# NE556-CD4069-Synth-Toy.net
KiCad netlist of a schematic drawn in EAGLE
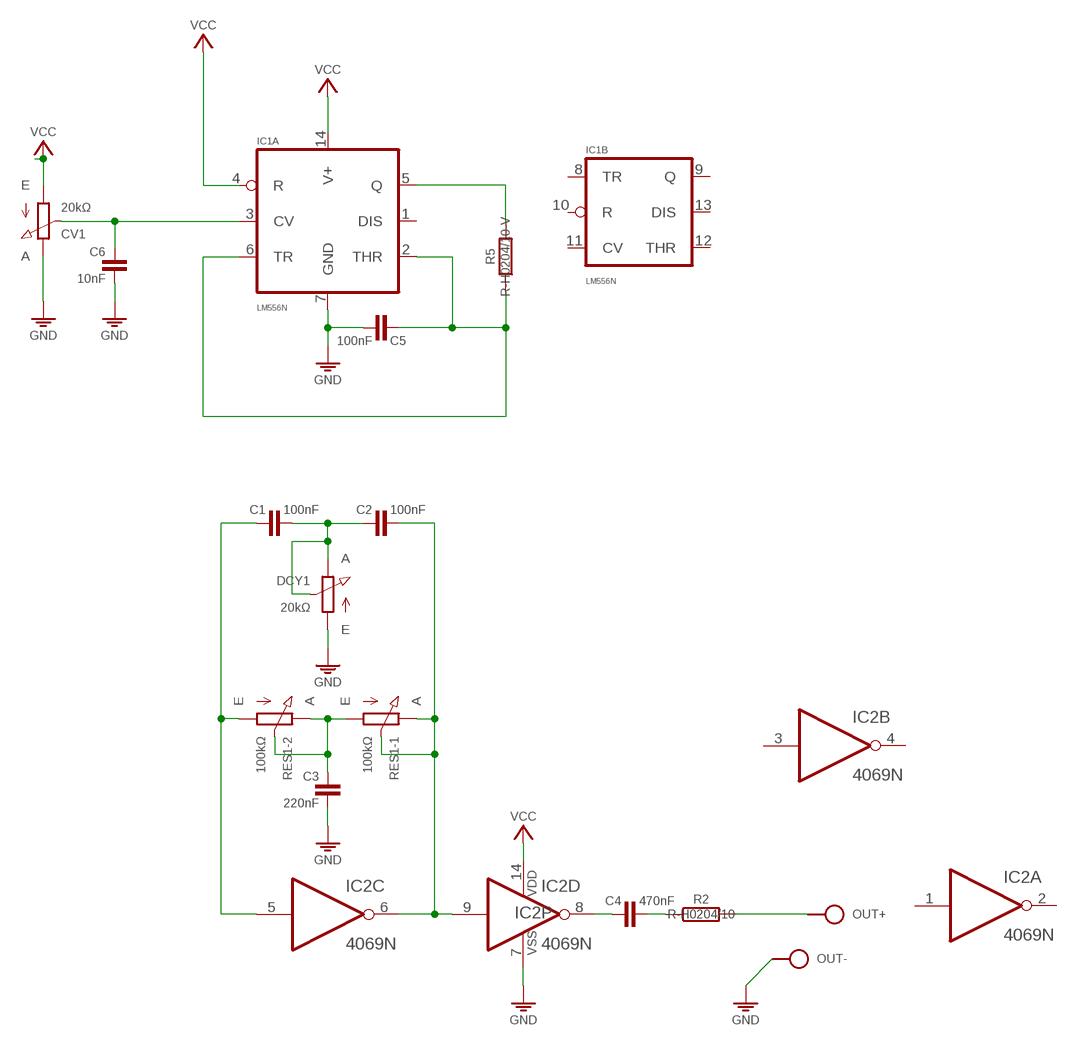
[diagram p0: schematic, sheet 1]

(export (version "E")
  (design (tool "Eeschema 10.0.6"))
  (components
    (comp (ref "C1")
      (value "100nF")
      (footprint "eagle-import:C050-024X044")
      (libsource (lib "eagle-import") (part "C-H050-024X044"))
    )
    (comp (ref "C2")
      (value "100nF")
      (footprint "eagle-import:C050-024X044")
      (libsource (lib "eagle-import") (part "C-H050-024X044"))
    )
    (comp (ref "C3")
      (value "220nF")
      (footprint "eagle-import:C050-020X044_V")
      (libsource (lib "eagle-import") (part "C050-020X044/V"))
    )
    (comp (ref "C4")
      (value "470nF")
      (footprint "eagle-import:C050-024X044")
      (libsource (lib "eagle-import") (part "C-H050-024X044"))
    )
    (comp (ref "C5")
      (value "100nF")
      (footprint "eagle-import:C050-020X044")
      (libsource (lib "eagle-import") (part "C-H050-020X044"))
    )
    (comp (ref "C6")
      (value "10nF")
      (footprint "eagle-import:C050-020X044_V")
      (libsource (lib "eagle-import") (part "C050-020X044/V"))
    )
    (comp (ref "CV1")
      (value "20kΩ")
      (footprint "eagle-import:POT")
      (libsource (lib "eagle-import") (part "POT"))
    )
    (comp (ref "DCY1")
      (value "20kΩ")
      (footprint "eagle-import:POT")
      (libsource (lib "eagle-import") (part "POT"))
    )
    (comp (ref "IC1")
      (value "LM556N")
      (footprint "eagle-import:DIL14")
      (libsource (lib "eagle-import") (part "556NLM"))
    )
    (comp (ref "IC2")
      (value "4069N")
      (footprint "eagle-import:DIL14")
      (libsource (lib "eagle-import") (part "4069N"))
    )
    (comp (ref "OUT")
      (value "SPAD+-+-")
      (footprint "eagle-import:SPAD+-")
      (libsource (lib "eagle-import") (part "SPAD+-+-"))
    )
    (comp (ref "R2")
      (value "R-H0204/10")
      (footprint "eagle-import:0204_10")
      (libsource (lib "eagle-import") (part "R-H0204/10"))
    )
    (comp (ref "R5")
      (value "R-H0204/10-V")
      (footprint "eagle-import:0204_10-V")
      (libsource (lib "eagle-import") (part "R-H0204/10-V"))
    )
    (comp (ref "RES1")
      (value "100kΩ")
      (footprint "eagle-import:POT-STEREO-2X3")
      (libsource (lib "eagle-import") (part "POT-STEREO"))
    )
    (comp (ref "S3")
      (value "VCC_GNDPWR-L")
      (footprint "eagle-import:PWR-L")
      (libsource (lib "eagle-import") (part "VCC_GNDPWR-L"))
    )
  )
  (nets
    (net (code "1") (name "GND") (class "Default")
      (node (ref "C3") (pin "2") (pinfunction "2_2") (pintype "passive"))
      (node (ref "C5") (pin "2") (pinfunction "2_2") (pintype "passive"))
      (node (ref "C6") (pin "2") (pinfunction "2_2") (pintype "passive"))
      (node (ref "CV1") (pin "E") (pinfunction "E_E") (pintype "passive"))
      (node (ref "DCY1") (pin "A") (pinfunction "A_A") (pintype "passive"))
      (node (ref "IC1") (pin "7") (pinfunction "GND_7") (pintype "power_in"))
      (node (ref "IC2") (pin "7") (pinfunction "VSS_7") (pintype "power_in"))
      (node (ref "OUT") (pin "1") (pinfunction "P$1_1") (pintype "passive"))
      (node (ref "S3") (pin "1") (pinfunction "GND_1") (pintype "power_in"))
    )
    (net (code "2") (name "Net-(C1-Pad2)") (class "Default")
      (node (ref "C1") (pin "2") (pinfunction "2_2") (pintype "passive"))
      (node (ref "C2") (pin "1") (pinfunction "1_1") (pintype "passive"))
      (node (ref "DCY1") (pin "E") (pinfunction "E_E") (pintype "passive"))
      (node (ref "DCY1") (pin "S") (pinfunction "S_S") (pintype "passive"))
    )
    (net (code "3") (name "Net-(C4-Pad2)") (class "Default")
      (node (ref "C4") (pin "2") (pinfunction "2_2") (pintype "passive"))
      (node (ref "R2") (pin "1") (pinfunction "1_1") (pintype "passive"))
    )
    (net (code "4") (name "Net-(IC1A-CV)") (class "Default")
      (node (ref "C6") (pin "1") (pinfunction "1_1") (pintype "passive"))
      (node (ref "CV1") (pin "S") (pinfunction "S_S") (pintype "passive"))
      (node (ref "IC1") (pin "3") (pinfunction "CV_3") (pintype "input"))
    )
    (net (code "5") (name "Net-(IC1A-Q)") (class "Default")
      (node (ref "IC1") (pin "5") (pinfunction "Q_5") (pintype "output"))
      (node (ref "R5") (pin "2") (pinfunction "2_2") (pintype "passive"))
    )
    (net (code "6") (name "Net-(IC1A-THR)") (class "Default")
      (node (ref "C5") (pin "1") (pinfunction "1_1") (pintype "passive"))
      (node (ref "IC1") (pin "2") (pinfunction "THR_2") (pintype "input"))
      (node (ref "IC1") (pin "6") (pinfunction "TR_6") (pintype "input"))
      (node (ref "R5") (pin "1") (pinfunction "1_1") (pintype "passive"))
    )
    (net (code "7") (name "Net-(IC2C-I)") (class "Default")
      (node (ref "C1") (pin "1") (pinfunction "1_1") (pintype "passive"))
      (node (ref "IC2") (pin "5") (pinfunction "I_5") (pintype "input"))
      (node (ref "RES1") (pin "2-A") (pinfunction "A_2-A") (pintype "passive"))
    )
    (net (code "8") (name "Net-(IC2C-O)") (class "Default")
      (node (ref "C2") (pin "2") (pinfunction "2_2") (pintype "passive"))
      (node (ref "IC2") (pin "6") (pinfunction "O_6") (pintype "output"))
      (node (ref "IC2") (pin "9") (pinfunction "I_9") (pintype "input"))
      (node (ref "RES1") (pin "1-E") (pinfunction "E_1-E") (pintype "passive"))
      (node (ref "RES1") (pin "1-S") (pinfunction "S_1-S") (pintype "passive"))
    )
    (net (code "9") (name "Net-(IC2D-O)") (class "Default")
      (node (ref "C4") (pin "1") (pinfunction "1_1") (pintype "passive"))
      (node (ref "IC2") (pin "8") (pinfunction "O_8") (pintype "output"))
    )
    (net (code "10") (name "Net-(OUTA-P$1)") (class "Default")
      (node (ref "OUT") (pin "2") (pinfunction "P$1_2") (pintype "passive"))
      (node (ref "R2") (pin "2") (pinfunction "2_2") (pintype "passive"))
    )
    (net (code "11") (name "Net-(RES1A-A)") (class "Default")
      (node (ref "C3") (pin "1") (pinfunction "1_1") (pintype "passive"))
      (node (ref "RES1") (pin "1-A") (pinfunction "A_1-A") (pintype "passive"))
      (node (ref "RES1") (pin "2-E") (pinfunction "E_2-E") (pintype "passive"))
      (node (ref "RES1") (pin "2-S") (pinfunction "S_2-S") (pintype "passive"))
    )
    (net (code "12") (name "VCC") (class "Default")
      (node (ref "CV1") (pin "A") (pinfunction "A_A") (pintype "passive"))
      (node (ref "IC1") (pin "14") (pinfunction "V+_14") (pintype "power_in"))
      (node (ref "IC1") (pin "4") (pinfunction "R_4") (pintype "input"))
      (node (ref "IC2") (pin "14") (pinfunction "VDD_14") (pintype "power_in"))
      (node (ref "S3") (pin "2") (pinfunction "VCC_2") (pintype "power_in"))
    )
    (net (code "13") (name "unconnected-(IC1A-DIS-Pad1)") (class "Default")
      (node (ref "IC1") (pin "1") (pinfunction "DIS_1") (pintype "passive"))
    )
    (net (code "14") (name "unconnected-(IC1B-CV-Pad11)") (class "Default")
      (node (ref "IC1") (pin "11") (pinfunction "CV_11") (pintype "input"))
    )
    (net (code "15") (name "unconnected-(IC1B-DIS-Pad13)") (class "Default")
      (node (ref "IC1") (pin "13") (pinfunction "DIS_13") (pintype "input"))
    )
    (net (code "16") (name "unconnected-(IC1B-Q-Pad9)") (class "Default")
      (node (ref "IC1") (pin "9") (pinfunction "Q_9") (pintype "output"))
    )
    (net (code "17") (name "unconnected-(IC1B-R-Pad10)") (class "Default")
      (node (ref "IC1") (pin "10") (pinfunction "R_10") (pintype "input"))
    )
    (net (code "18") (name "unconnected-(IC1B-THR-Pad12)") (class "Default")
      (node (ref "IC1") (pin "12") (pinfunction "THR_12") (pintype "input"))
    )
    (net (code "19") (name "unconnected-(IC1B-TR-Pad8)") (class "Default")
      (node (ref "IC1") (pin "8") (pinfunction "TR_8") (pintype "input"))
    )
    (net (code "20") (name "unconnected-(IC2A-I-Pad1)") (class "Default")
      (node (ref "IC2") (pin "1") (pinfunction "I_1") (pintype "input"))
    )
    (net (code "21") (name "unconnected-(IC2A-O-Pad2)") (class "Default")
      (node (ref "IC2") (pin "2") (pinfunction "O_2") (pintype "output"))
    )
    (net (code "22") (name "unconnected-(IC2B-I-Pad3)") (class "Default")
      (node (ref "IC2") (pin "3") (pinfunction "I_3") (pintype "input"))
    )
    (net (code "23") (name "unconnected-(IC2B-O-Pad4)") (class "Default")
      (node (ref "IC2") (pin "4") (pinfunction "O_4") (pintype "output"))
    )
  )
)
